# REGULADORES.net
KiCad netlist of a schematic drawn in Altium Designer
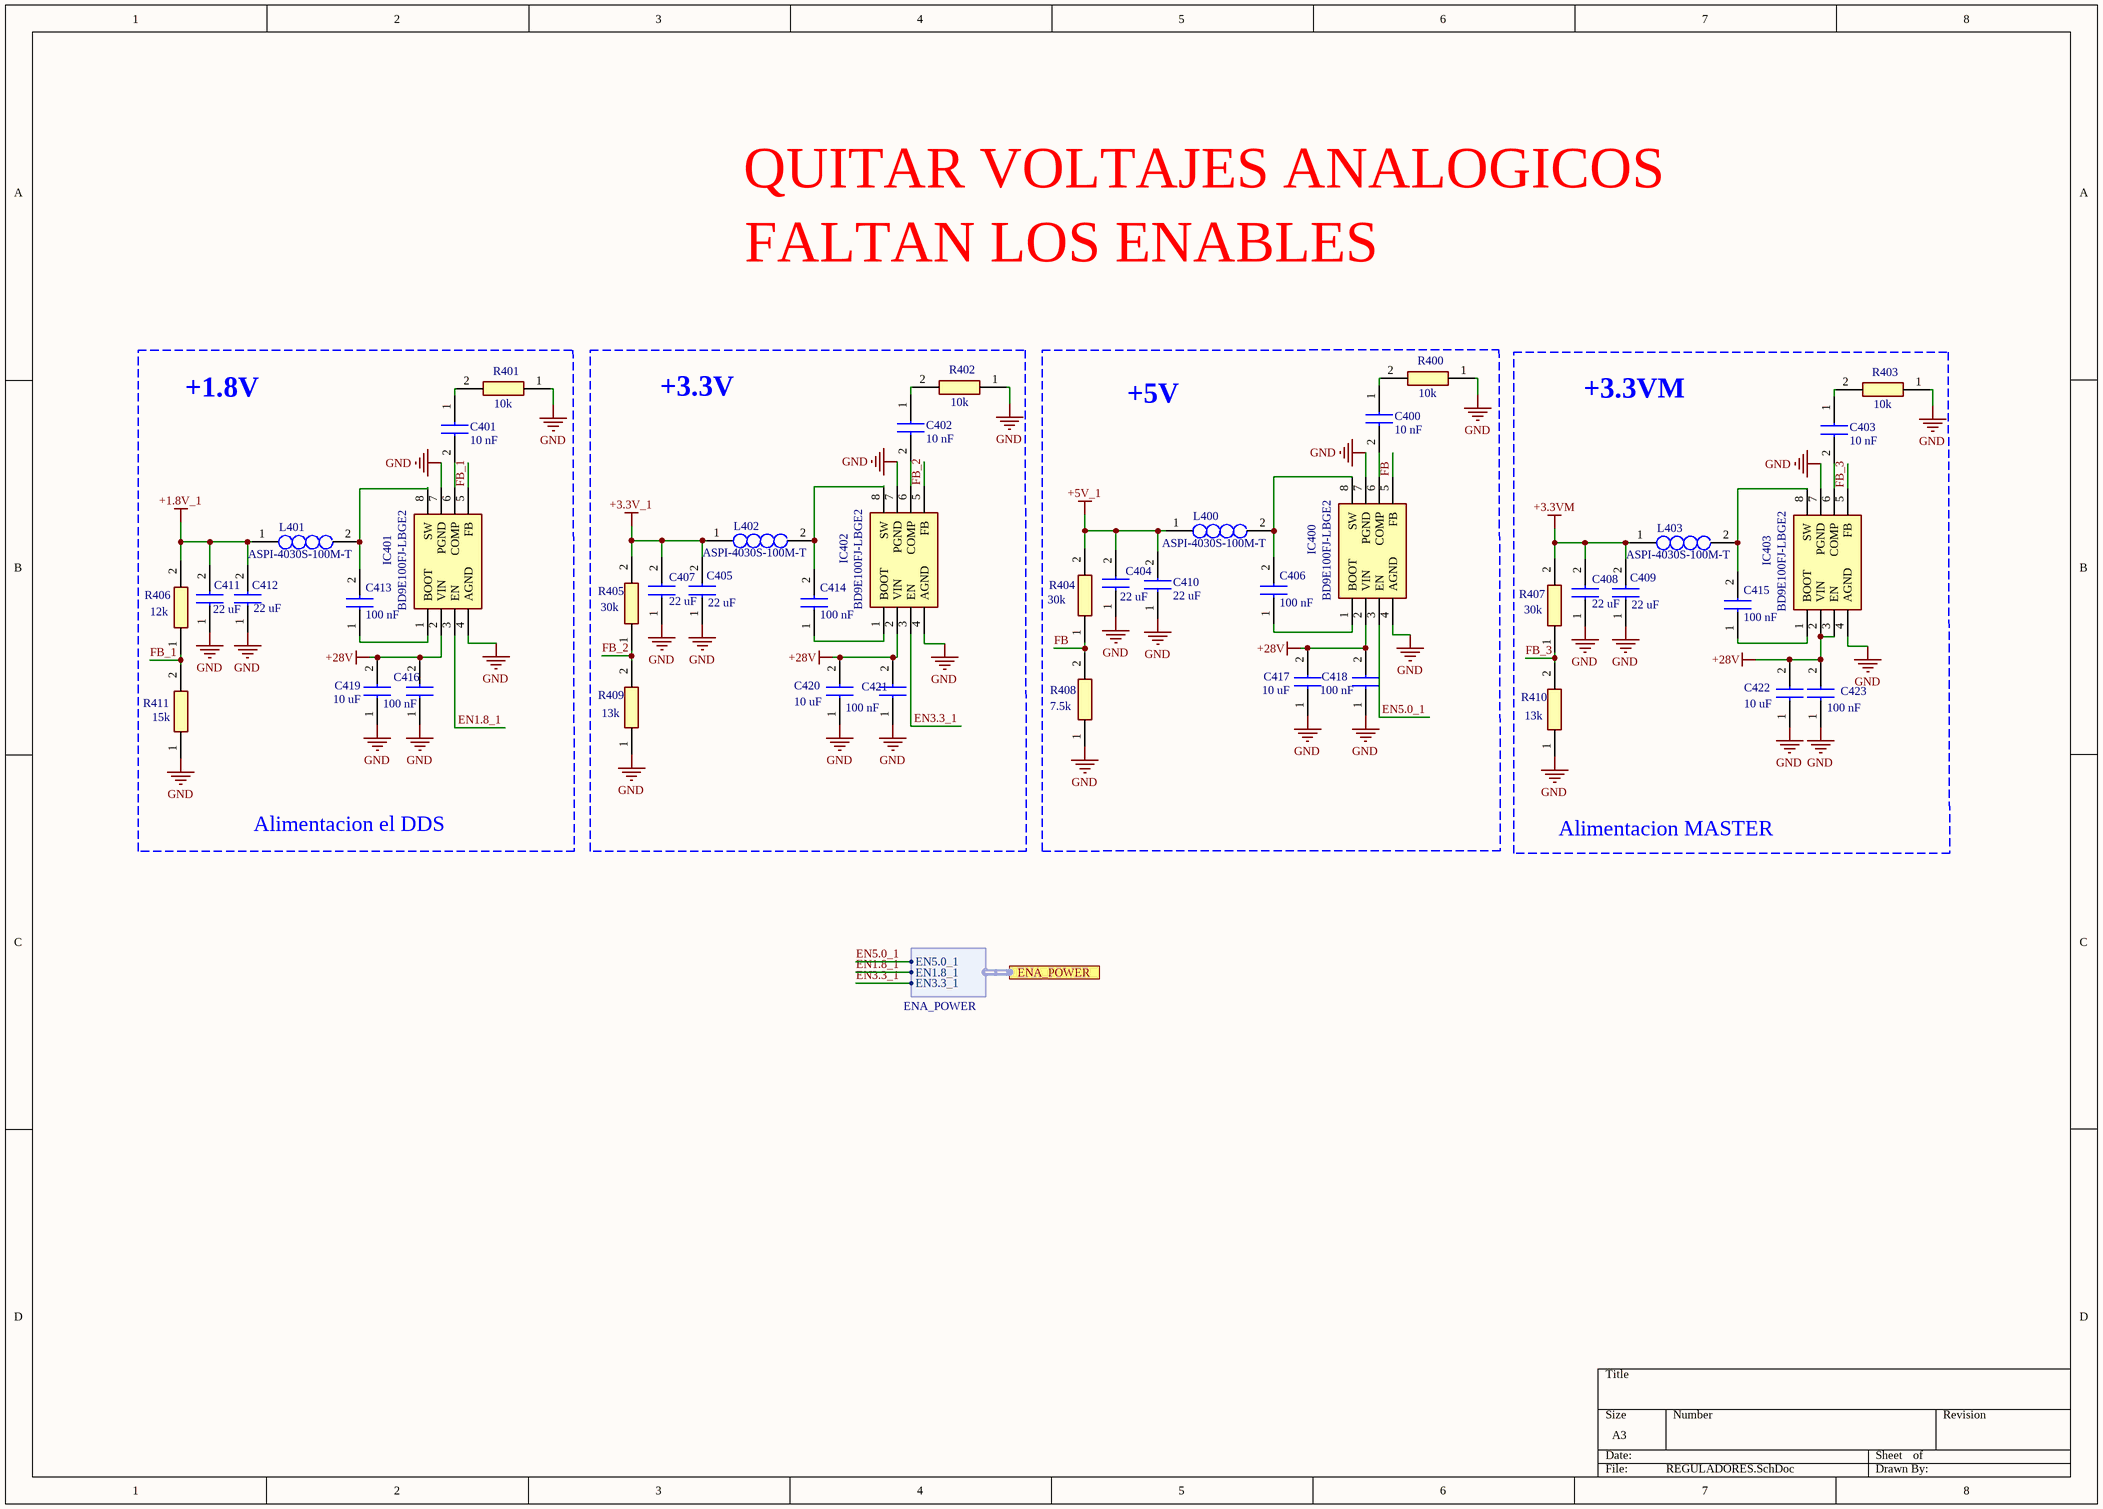
[diagram p0: REGULADORES.SchDoc]

(export (version "E")
  (design (tool "Eeschema 10.0.6"))
  (components
    (comp (ref "C400")
      (value "10 nF")
      (footprint "SamacSys:C0603")
      (description "Capacitor")
      (fields (field (name "MANUFACTURER_PART_NUMBER") "C0603H470J5GACTU"))
      (libsource (lib "*") (part "C0603H470J5GACTU"))
    )
    (comp (ref "C401")
      (value "10 nF")
      (footprint "SamacSys:C0603")
      (description "Capacitor")
      (fields (field (name "MANUFACTURER_PART_NUMBER") "C0603H470J5GACTU"))
      (libsource (lib "LIBRERIA_GEN_V2.0") (part "C0603H470J5GACTU"))
    )
    (comp (ref "C402")
      (value "10 nF")
      (footprint "SamacSys:C0603")
      (description "Capacitor")
      (fields (field (name "MANUFACTURER_PART_NUMBER") "C0603H470J5GACTU"))
      (libsource (lib "LIBRERIA_GEN_V2.0") (part "C0603H470J5GACTU"))
    )
    (comp (ref "C403")
      (value "10 nF")
      (footprint "SamacSys:C0603")
      (description "Capacitor")
      (fields (field (name "MANUFACTURER_PART_NUMBER") "C0603H470J5GACTU"))
      (libsource (lib "LIBRERIA_GEN_V2.0") (part "C0603H470J5GACTU"))
    )
    (comp (ref "C404")
      (value "22 uF")
      (footprint "SamacSys:CAPC3216X94N")
      (description "Capacitor")
      (fields
        (field (name "MANUFACTURER_PART_NUMBER") "KAM31BR81H103KT")
        (field (name "MOUSER PART NUMBER") "581-KAM31BR81H103KT")
      )
      (libsource (lib "LIBRERIA_GEN_V2.0") (part "KAM31BR81H103KT"))
    )
    (comp (ref "C405")
      (value "22 uF")
      (footprint "SamacSys:CAPC3216X94N")
      (description "Capacitor")
      (fields
        (field (name "MANUFACTURER_PART_NUMBER") "KAM31BR81H103KT")
        (field (name "MOUSER PART NUMBER") "581-KAM31BR81H103KT")
      )
      (libsource (lib "LIBRERIA_GEN_V2.0") (part "KAM31BR81H103KT"))
    )
    (comp (ref "C406")
      (value "100 nF")
      (footprint "SamacSys:C0603")
      (description "Capacitor")
      (fields (field (name "MANUFACTURER_PART_NUMBER") "C0603H470J5GACTU"))
      (libsource (lib "*") (part "C0603H470J5GACTU"))
    )
    (comp (ref "C407")
      (value "22 uF")
      (footprint "SamacSys:CAPC3216X94N")
      (description "Capacitor")
      (fields
        (field (name "MANUFACTURER_PART_NUMBER") "KAM31BR81H103KT")
        (field (name "MOUSER PART NUMBER") "581-KAM31BR81H103KT")
      )
      (libsource (lib "LIBRERIA_GEN_V2.0") (part "KAM31BR81H103KT"))
    )
    (comp (ref "C408")
      (value "22 uF")
      (footprint "SamacSys:CAPC3216X94N")
      (description "Capacitor")
      (fields
        (field (name "MANUFACTURER_PART_NUMBER") "KAM31BR81H103KT")
        (field (name "MOUSER PART NUMBER") "581-KAM31BR81H103KT")
      )
      (libsource (lib "LIBRERIA_GEN_V2.0") (part "KAM31BR81H103KT"))
    )
    (comp (ref "C409")
      (value "22 uF")
      (footprint "SamacSys:CAPC3216X94N")
      (description "Capacitor")
      (fields
        (field (name "MANUFACTURER_PART_NUMBER") "KAM31BR81H103KT")
        (field (name "MOUSER PART NUMBER") "581-KAM31BR81H103KT")
      )
      (libsource (lib "LIBRERIA_GEN_V2.0") (part "KAM31BR81H103KT"))
    )
    (comp (ref "C410")
      (value "22 uF")
      (footprint "SamacSys:CAPC3216X94N")
      (description "Capacitor")
      (fields
        (field (name "MANUFACTURER_PART_NUMBER") "KAM31BR81H103KT")
        (field (name "MOUSER PART NUMBER") "581-KAM31BR81H103KT")
      )
      (libsource (lib "LIBRERIA_GEN_V2.0") (part "KAM31BR81H103KT"))
    )
    (comp (ref "C411")
      (value "22 uF")
      (footprint "SamacSys:CAPC3216X94N")
      (description "Capacitor")
      (fields
        (field (name "MANUFACTURER_PART_NUMBER") "KAM31BR81H103KT")
        (field (name "MOUSER PART NUMBER") "581-KAM31BR81H103KT")
      )
      (libsource (lib "LIBRERIA_GEN_V2.0") (part "KAM31BR81H103KT"))
    )
    (comp (ref "C412")
      (value "22 uF")
      (footprint "SamacSys:CAPC3216X94N")
      (description "Capacitor")
      (fields
        (field (name "MANUFACTURER_PART_NUMBER") "KAM31BR81H103KT")
        (field (name "MOUSER PART NUMBER") "581-KAM31BR81H103KT")
      )
      (libsource (lib "LIBRERIA_GEN_V2.0") (part "KAM31BR81H103KT"))
    )
    (comp (ref "C413")
      (value "100 nF")
      (footprint "SamacSys:C0603")
      (description "Capacitor")
      (fields (field (name "MANUFACTURER_PART_NUMBER") "C0603H470J5GACTU"))
      (libsource (lib "LIBRERIA_GEN_V2.0") (part "C0603H470J5GACTU"))
    )
    (comp (ref "C414")
      (value "100 nF")
      (footprint "SamacSys:C0603")
      (description "Capacitor")
      (fields (field (name "MANUFACTURER_PART_NUMBER") "C0603H470J5GACTU"))
      (libsource (lib "LIBRERIA_GEN_V2.0") (part "C0603H470J5GACTU"))
    )
    (comp (ref "C415")
      (value "100 nF")
      (footprint "SamacSys:C0603")
      (description "Capacitor")
      (fields (field (name "MANUFACTURER_PART_NUMBER") "C0603H470J5GACTU"))
      (libsource (lib "LIBRERIA_GEN_V2.0") (part "C0603H470J5GACTU"))
    )
    (comp (ref "C416")
      (value "100 nF")
      (footprint "SamacSys:CAPC3216X94N")
      (description "Capacitor")
      (fields
        (field (name "MANUFACTURER_PART_NUMBER") "KAM31BR81H103KT")
        (field (name "MOUSER PART NUMBER") "581-KAM31BR81H103KT")
      )
      (libsource (lib "LIBRERIA_GEN_V2.0") (part "KAM31BR81H103KT"))
    )
    (comp (ref "C417")
      (value "10 uF")
      (footprint "SamacSys:CAPC3216X94N")
      (description "Capacitor")
      (fields
        (field (name "MANUFACTURER_PART_NUMBER") "KAM31BR81H103KT")
        (field (name "MOUSER PART NUMBER") "581-KAM31BR81H103KT")
      )
      (libsource (lib "LIBRERIA_GEN_V2.0") (part "KAM31BR81H103KT"))
    )
    (comp (ref "C418")
      (value "100 nF")
      (footprint "SamacSys:CAPC3216X94N")
      (description "Capacitor")
      (fields
        (field (name "MANUFACTURER_PART_NUMBER") "KAM31BR81H103KT")
        (field (name "MOUSER PART NUMBER") "581-KAM31BR81H103KT")
      )
      (libsource (lib "LIBRERIA_GEN_V2.0") (part "KAM31BR81H103KT"))
    )
    (comp (ref "C419")
      (value "10 uF")
      (footprint "SamacSys:CAPC3216X94N")
      (description "Capacitor")
      (fields
        (field (name "MANUFACTURER_PART_NUMBER") "KAM31BR81H103KT")
        (field (name "MOUSER PART NUMBER") "581-KAM31BR81H103KT")
      )
      (libsource (lib "LIBRERIA_GEN_V2.0") (part "KAM31BR81H103KT"))
    )
    (comp (ref "C420")
      (value "10 uF")
      (footprint "SamacSys:CAPC3216X94N")
      (description "Capacitor")
      (fields
        (field (name "MANUFACTURER_PART_NUMBER") "KAM31BR81H103KT")
        (field (name "MOUSER PART NUMBER") "581-KAM31BR81H103KT")
      )
      (libsource (lib "LIBRERIA_GEN_V2.0") (part "KAM31BR81H103KT"))
    )
    (comp (ref "C421")
      (value "100 nF")
      (footprint "SamacSys:CAPC3216X94N")
      (description "Capacitor")
      (fields
        (field (name "MANUFACTURER_PART_NUMBER") "KAM31BR81H103KT")
        (field (name "MOUSER PART NUMBER") "581-KAM31BR81H103KT")
      )
      (libsource (lib "LIBRERIA_GEN_V2.0") (part "KAM31BR81H103KT"))
    )
    (comp (ref "C422")
      (value "10 uF")
      (footprint "SamacSys:CAPC3216X94N")
      (description "Capacitor")
      (fields
        (field (name "MANUFACTURER_PART_NUMBER") "KAM31BR81H103KT")
        (field (name "MOUSER PART NUMBER") "581-KAM31BR81H103KT")
      )
      (libsource (lib "LIBRERIA_GEN_V2.0") (part "KAM31BR81H103KT"))
    )
    (comp (ref "C423")
      (value "100 nF")
      (footprint "SamacSys:CAPC3216X94N")
      (description "Capacitor")
      (fields
        (field (name "MANUFACTURER_PART_NUMBER") "KAM31BR81H103KT")
        (field (name "MOUSER PART NUMBER") "581-KAM31BR81H103KT")
      )
      (libsource (lib "LIBRERIA_GEN_V2.0") (part "KAM31BR81H103KT"))
    )
    (comp (ref "IC400")
      (value "BD9E100FJ-LBGE2")
      (footprint "SamacSys:SOIC127P600X165-8N")
      (description "Integrated Circuit")
      (fields (field (name "MOUSER PART NUMBER") "755-BD9E100FJ-LBGE2"))
      (libsource (lib "*") (part "BD9E100FJ-LBGE2"))
    )
    (comp (ref "IC401")
      (value "BD9E100FJ-LBGE2")
      (footprint "SamacSys:SOIC127P600X165-8N")
      (description "Integrated Circuit")
      (fields (field (name "MOUSER PART NUMBER") "755-BD9E100FJ-LBGE2"))
      (libsource (lib "LIBRERIA_GEN_V2.0") (part "BD9E100FJ-LBGE2"))
    )
    (comp (ref "IC402")
      (value "BD9E100FJ-LBGE2")
      (footprint "SamacSys:SOIC127P600X165-8N")
      (description "Integrated Circuit")
      (fields (field (name "MOUSER PART NUMBER") "755-BD9E100FJ-LBGE2"))
      (libsource (lib "LIBRERIA_GEN_V2.0") (part "BD9E100FJ-LBGE2"))
    )
    (comp (ref "IC403")
      (value "BD9E100FJ-LBGE2")
      (footprint "SamacSys:SOIC127P600X165-8N")
      (description "Integrated Circuit")
      (fields (field (name "MOUSER PART NUMBER") "755-BD9E100FJ-LBGE2"))
      (libsource (lib "LIBRERIA_GEN_V2.0") (part "BD9E100FJ-LBGE2"))
    )
    (comp (ref "L400")
      (value "ASPI-4030S-100M-T")
      (footprint "SamacSys:ASPI-4030S")
      (description "Inductor")
      (fields (field (name "MOUSER PART NUMBER") "815-ASPI-4030S-100MT"))
      (libsource (lib "*") (part "ASPI-4030S-100M-T"))
    )
    (comp (ref "L401")
      (value "ASPI-4030S-100M-T")
      (footprint "SamacSys:ASPI-4030S")
      (description "Inductor")
      (fields (field (name "MOUSER PART NUMBER") "815-ASPI-4030S-100MT"))
      (libsource (lib "LIBRERIA_GEN_V2.0") (part "ASPI-4030S-100M-T"))
    )
    (comp (ref "L402")
      (value "ASPI-4030S-100M-T")
      (footprint "SamacSys:ASPI-4030S")
      (description "Inductor")
      (fields (field (name "MOUSER PART NUMBER") "815-ASPI-4030S-100MT"))
      (libsource (lib "LIBRERIA_GEN_V2.0") (part "ASPI-4030S-100M-T"))
    )
    (comp (ref "L403")
      (value "ASPI-4030S-100M-T")
      (footprint "SamacSys:ASPI-4030S")
      (description "Inductor")
      (fields (field (name "MOUSER PART NUMBER") "815-ASPI-4030S-100MT"))
      (libsource (lib "LIBRERIA_GEN_V2.0") (part "ASPI-4030S-100M-T"))
    )
    (comp (ref "R400")
      (value "10k")
      (footprint "SamacSys:RESC1608X55N")
      (description "Resistor")
      (fields
        (field (name "MANUFACTURER_PART_NUMBER") "CR0603-FX-1431ELF")
        (field (name "MOUSER PART NUMBER") "652-CR0603FX-1431ELF")
      )
      (libsource (lib "*") (part "CR0603-FX-1431ELF"))
    )
    (comp (ref "R401")
      (value "10k")
      (footprint "SamacSys:RESC1608X55N")
      (description "Resistor")
      (fields
        (field (name "MANUFACTURER_PART_NUMBER") "CR0603-FX-1431ELF")
        (field (name "MOUSER PART NUMBER") "652-CR0603FX-1431ELF")
      )
      (libsource (lib "") (part "CR0603-FX-1431ELF_1"))
    )
    (comp (ref "R402")
      (value "10k")
      (footprint "SamacSys:RESC1608X55N")
      (description "Resistor")
      (fields
        (field (name "MANUFACTURER_PART_NUMBER") "CR0603-FX-1431ELF")
        (field (name "MOUSER PART NUMBER") "652-CR0603FX-1431ELF")
      )
      (libsource (lib "") (part "CR0603-FX-1431ELF_1"))
    )
    (comp (ref "R403")
      (value "10k")
      (footprint "SamacSys:RESC1608X55N")
      (description "Resistor")
      (fields
        (field (name "MANUFACTURER_PART_NUMBER") "CR0603-FX-1431ELF")
        (field (name "MOUSER PART NUMBER") "652-CR0603FX-1431ELF")
      )
      (libsource (lib "") (part "CR0603-FX-1431ELF_1"))
    )
    (comp (ref "R404")
      (value "30k")
      (footprint "SamacSys:RESC1608X55N")
      (description "Resistor")
      (fields
        (field (name "MANUFACTURER_PART_NUMBER") "CR0603-FX-1431ELF")
        (field (name "MOUSER PART NUMBER") "652-CR0603FX-1431ELF")
      )
      (libsource (lib "") (part "CR0603-FX-1431ELF_1"))
    )
    (comp (ref "R405")
      (value "30k")
      (footprint "SamacSys:RESC1608X55N")
      (description "Resistor")
      (fields
        (field (name "MANUFACTURER_PART_NUMBER") "CR0603-FX-1431ELF")
        (field (name "MOUSER PART NUMBER") "652-CR0603FX-1431ELF")
      )
      (libsource (lib "LIBRERIA_GEN_V2.0") (part "CR0603-FX-1431ELF"))
    )
    (comp (ref "R406")
      (value "12k")
      (footprint "SamacSys:RESC1608X55N")
      (description "Resistor")
      (fields
        (field (name "MANUFACTURER_PART_NUMBER") "CR0603-FX-1431ELF")
        (field (name "MOUSER PART NUMBER") "652-CR0603FX-1431ELF")
      )
      (libsource (lib "LIBRERIA_GEN_V2.0") (part "CR0603-FX-1431ELF"))
    )
    (comp (ref "R407")
      (value "30k")
      (footprint "SamacSys:RESC1608X55N")
      (description "Resistor")
      (fields
        (field (name "MANUFACTURER_PART_NUMBER") "CR0603-FX-1431ELF")
        (field (name "MOUSER PART NUMBER") "652-CR0603FX-1431ELF")
      )
      (libsource (lib "LIBRERIA_GEN_V2.0") (part "CR0603-FX-1431ELF"))
    )
    (comp (ref "R408")
      (value "7.5k")
      (footprint "SamacSys:RESC1608X55N")
      (description "Resistor")
      (fields
        (field (name "MANUFACTURER_PART_NUMBER") "CR0603-FX-1431ELF")
        (field (name "MOUSER PART NUMBER") "652-CR0603FX-1431ELF")
      )
      (libsource (lib "") (part "CR0603-FX-1431ELF_1"))
    )
    (comp (ref "R409")
      (value "13k")
      (footprint "SamacSys:RESC1608X55N")
      (description "Resistor")
      (fields
        (field (name "MANUFACTURER_PART_NUMBER") "CR0603-FX-1431ELF")
        (field (name "MOUSER PART NUMBER") "652-CR0603FX-1431ELF")
      )
      (libsource (lib "LIBRERIA_GEN_V2.0") (part "CR0603-FX-1431ELF"))
    )
    (comp (ref "R410")
      (value "13k")
      (footprint "SamacSys:RESC1608X55N")
      (description "Resistor")
      (fields
        (field (name "MANUFACTURER_PART_NUMBER") "CR0603-FX-1431ELF")
        (field (name "MOUSER PART NUMBER") "652-CR0603FX-1431ELF")
      )
      (libsource (lib "LIBRERIA_GEN_V2.0") (part "CR0603-FX-1431ELF"))
    )
    (comp (ref "R411")
      (value "15k")
      (footprint "SamacSys:RESC1608X55N")
      (description "Resistor")
      (fields
        (field (name "MANUFACTURER_PART_NUMBER") "CR0603-FX-1431ELF")
        (field (name "MOUSER PART NUMBER") "652-CR0603FX-1431ELF")
      )
      (libsource (lib "LIBRERIA_GEN_V2.0") (part "CR0603-FX-1431ELF"))
    )
  )
  (nets
    (net (code "2") (name "+1.8V_1") (class "Default")
      (node (ref "C411") (pin "2") (pinfunction "2_2") (pintype "passive"))
      (node (ref "C412") (pin "2") (pinfunction "2_2") (pintype "passive"))
      (node (ref "L401") (pin "1") (pinfunction "1_1") (pintype "passive"))
      (node (ref "R406") (pin "2") (pinfunction "2_2") (pintype "passive"))
    )
    (net (code "3") (name "+3.3VM") (class "Default")
      (node (ref "C408") (pin "2") (pinfunction "2_2") (pintype "passive"))
      (node (ref "C409") (pin "2") (pinfunction "2_2") (pintype "passive"))
      (node (ref "L403") (pin "1") (pinfunction "1_1") (pintype "passive"))
      (node (ref "R407") (pin "2") (pinfunction "2_2") (pintype "passive"))
    )
    (net (code "4") (name "+3.3V_1") (class "Default")
      (node (ref "C405") (pin "2") (pinfunction "2_2") (pintype "passive"))
      (node (ref "C407") (pin "2") (pinfunction "2_2") (pintype "passive"))
      (node (ref "L402") (pin "1") (pinfunction "1_1") (pintype "passive"))
      (node (ref "R405") (pin "2") (pinfunction "2_2") (pintype "passive"))
    )
    (net (code "5") (name "+5V_1") (class "Default")
      (node (ref "C404") (pin "2") (pinfunction "2_2") (pintype "passive"))
      (node (ref "C410") (pin "2") (pinfunction "2_2") (pintype "passive"))
      (node (ref "L400") (pin "1") (pinfunction "1_1") (pintype "passive"))
      (node (ref "R404") (pin "2") (pinfunction "2_2") (pintype "passive"))
    )
    (net (code "6") (name "+28V") (class "Default")
      (node (ref "C416") (pin "2") (pinfunction "2_2") (pintype "passive"))
      (node (ref "C417") (pin "2") (pinfunction "2_2") (pintype "passive"))
      (node (ref "C418") (pin "2") (pinfunction "2_2") (pintype "passive"))
      (node (ref "C419") (pin "2") (pinfunction "2_2") (pintype "passive"))
      (node (ref "C420") (pin "2") (pinfunction "2_2") (pintype "passive"))
      (node (ref "C421") (pin "2") (pinfunction "2_2") (pintype "passive"))
      (node (ref "C422") (pin "2") (pinfunction "2_2") (pintype "passive"))
      (node (ref "C423") (pin "2") (pinfunction "2_2") (pintype "passive"))
      (node (ref "IC400") (pin "2") (pinfunction "VIN_2") (pintype "passive"))
      (node (ref "IC401") (pin "2") (pinfunction "VIN_2") (pintype "passive"))
      (node (ref "IC402") (pin "2") (pinfunction "VIN_2") (pintype "passive"))
      (node (ref "IC403") (pin "2") (pinfunction "VIN_2") (pintype "passive"))
      (node (ref "IC403") (pin "3") (pinfunction "EN_3") (pintype "passive"))
    )
    (net (code "7") (name "/EN1.8_1") (class "Default")
      (node (ref "IC401") (pin "3") (pinfunction "EN_3") (pintype "passive"))
    )
    (net (code "8") (name "/EN3.3_1") (class "Default")
      (node (ref "IC402") (pin "3") (pinfunction "EN_3") (pintype "passive"))
    )
    (net (code "9") (name "/EN5.0_1") (class "Default")
      (node (ref "IC400") (pin "3") (pinfunction "EN_3") (pintype "passive"))
    )
    (net (code "10") (name "/FB") (class "Default")
      (node (ref "IC400") (pin "5") (pinfunction "FB_5") (pintype "passive"))
      (node (ref "R404") (pin "1") (pinfunction "1_1") (pintype "passive"))
      (node (ref "R408") (pin "2") (pinfunction "2_2") (pintype "passive"))
    )
    (net (code "11") (name "/FB_1") (class "Default")
      (node (ref "IC401") (pin "5") (pinfunction "FB_5") (pintype "passive"))
      (node (ref "R406") (pin "1") (pinfunction "1_1") (pintype "passive"))
      (node (ref "R411") (pin "2") (pinfunction "2_2") (pintype "passive"))
    )
    (net (code "12") (name "/FB_2") (class "Default")
      (node (ref "IC402") (pin "5") (pinfunction "FB_5") (pintype "passive"))
      (node (ref "R405") (pin "1") (pinfunction "1_1") (pintype "passive"))
      (node (ref "R409") (pin "2") (pinfunction "2_2") (pintype "passive"))
    )
    (net (code "13") (name "/FB_3") (class "Default")
      (node (ref "IC403") (pin "5") (pinfunction "FB_5") (pintype "passive"))
      (node (ref "R407") (pin "1") (pinfunction "1_1") (pintype "passive"))
      (node (ref "R410") (pin "2") (pinfunction "2_2") (pintype "passive"))
    )
    (net (code "15") (name "GND") (class "Default")
      (node (ref "C404") (pin "1") (pinfunction "1_1") (pintype "passive"))
      (node (ref "C405") (pin "1") (pinfunction "1_1") (pintype "passive"))
      (node (ref "C407") (pin "1") (pinfunction "1_1") (pintype "passive"))
      (node (ref "C408") (pin "1") (pinfunction "1_1") (pintype "passive"))
      (node (ref "C409") (pin "1") (pinfunction "1_1") (pintype "passive"))
      (node (ref "C410") (pin "1") (pinfunction "1_1") (pintype "passive"))
      (node (ref "C411") (pin "1") (pinfunction "1_1") (pintype "passive"))
      (node (ref "C412") (pin "1") (pinfunction "1_1") (pintype "passive"))
      (node (ref "C416") (pin "1") (pinfunction "1_1") (pintype "passive"))
      (node (ref "C417") (pin "1") (pinfunction "1_1") (pintype "passive"))
      (node (ref "C418") (pin "1") (pinfunction "1_1") (pintype "passive"))
      (node (ref "C419") (pin "1") (pinfunction "1_1") (pintype "passive"))
      (node (ref "C420") (pin "1") (pinfunction "1_1") (pintype "passive"))
      (node (ref "C421") (pin "1") (pinfunction "1_1") (pintype "passive"))
      (node (ref "C422") (pin "1") (pinfunction "1_1") (pintype "passive"))
      (node (ref "C423") (pin "1") (pinfunction "1_1") (pintype "passive"))
      (node (ref "IC400") (pin "4") (pinfunction "AGND_4") (pintype "passive"))
      (node (ref "IC400") (pin "7") (pinfunction "PGND_7") (pintype "passive"))
      (node (ref "IC401") (pin "4") (pinfunction "AGND_4") (pintype "passive"))
      (node (ref "IC401") (pin "7") (pinfunction "PGND_7") (pintype "passive"))
      (node (ref "IC402") (pin "4") (pinfunction "AGND_4") (pintype "passive"))
      (node (ref "IC402") (pin "7") (pinfunction "PGND_7") (pintype "passive"))
      (node (ref "IC403") (pin "4") (pinfunction "AGND_4") (pintype "passive"))
      (node (ref "IC403") (pin "7") (pinfunction "PGND_7") (pintype "passive"))
      (node (ref "R400") (pin "1") (pinfunction "1_1") (pintype "passive"))
      (node (ref "R401") (pin "1") (pinfunction "1_1") (pintype "passive"))
      (node (ref "R402") (pin "1") (pinfunction "1_1") (pintype "passive"))
      (node (ref "R403") (pin "1") (pinfunction "1_1") (pintype "passive"))
      (node (ref "R408") (pin "1") (pinfunction "1_1") (pintype "passive"))
      (node (ref "R409") (pin "1") (pinfunction "1_1") (pintype "passive"))
      (node (ref "R410") (pin "1") (pinfunction "1_1") (pintype "passive"))
      (node (ref "R411") (pin "1") (pinfunction "1_1") (pintype "passive"))
    )
    (net (code "16") (name "Net-(C400-Pad1)") (class "Default")
      (node (ref "C400") (pin "1") (pinfunction "1_1") (pintype "passive"))
      (node (ref "R400") (pin "2") (pinfunction "2_2") (pintype "passive"))
    )
    (net (code "17") (name "Net-(C401-Pad1)") (class "Default")
      (node (ref "C401") (pin "1") (pinfunction "1_1") (pintype "passive"))
      (node (ref "R401") (pin "2") (pinfunction "2_2") (pintype "passive"))
    )
    (net (code "18") (name "Net-(C402-Pad1)") (class "Default")
      (node (ref "C402") (pin "1") (pinfunction "1_1") (pintype "passive"))
      (node (ref "R402") (pin "2") (pinfunction "2_2") (pintype "passive"))
    )
    (net (code "19") (name "Net-(C403-Pad1)") (class "Default")
      (node (ref "C403") (pin "1") (pinfunction "1_1") (pintype "passive"))
      (node (ref "R403") (pin "2") (pinfunction "2_2") (pintype "passive"))
    )
    (net (code "20") (name "Net-(IC400-BOOT)") (class "Default")
      (node (ref "C406") (pin "1") (pinfunction "1_1") (pintype "passive"))
      (node (ref "IC400") (pin "1") (pinfunction "BOOT_1") (pintype "passive"))
    )
    (net (code "21") (name "Net-(IC400-COMP)") (class "Default")
      (node (ref "C400") (pin "2") (pinfunction "2_2") (pintype "passive"))
      (node (ref "IC400") (pin "6") (pinfunction "COMP_6") (pintype "passive"))
    )
    (net (code "22") (name "Net-(IC400-SW)") (class "Default")
      (node (ref "C406") (pin "2") (pinfunction "2_2") (pintype "passive"))
      (node (ref "IC400") (pin "8") (pinfunction "SW_8") (pintype "passive"))
      (node (ref "L400") (pin "2") (pinfunction "2_2") (pintype "passive"))
    )
    (net (code "23") (name "Net-(IC401-BOOT)") (class "Default")
      (node (ref "C413") (pin "1") (pinfunction "1_1") (pintype "passive"))
      (node (ref "IC401") (pin "1") (pinfunction "BOOT_1") (pintype "passive"))
    )
    (net (code "24") (name "Net-(IC401-COMP)") (class "Default")
      (node (ref "C401") (pin "2") (pinfunction "2_2") (pintype "passive"))
      (node (ref "IC401") (pin "6") (pinfunction "COMP_6") (pintype "passive"))
    )
    (net (code "25") (name "Net-(IC401-SW)") (class "Default")
      (node (ref "C413") (pin "2") (pinfunction "2_2") (pintype "passive"))
      (node (ref "IC401") (pin "8") (pinfunction "SW_8") (pintype "passive"))
      (node (ref "L401") (pin "2") (pinfunction "2_2") (pintype "passive"))
    )
    (net (code "26") (name "Net-(IC402-BOOT)") (class "Default")
      (node (ref "C414") (pin "1") (pinfunction "1_1") (pintype "passive"))
      (node (ref "IC402") (pin "1") (pinfunction "BOOT_1") (pintype "passive"))
    )
    (net (code "27") (name "Net-(IC402-COMP)") (class "Default")
      (node (ref "C402") (pin "2") (pinfunction "2_2") (pintype "passive"))
      (node (ref "IC402") (pin "6") (pinfunction "COMP_6") (pintype "passive"))
    )
    (net (code "28") (name "Net-(IC402-SW)") (class "Default")
      (node (ref "C414") (pin "2") (pinfunction "2_2") (pintype "passive"))
      (node (ref "IC402") (pin "8") (pinfunction "SW_8") (pintype "passive"))
      (node (ref "L402") (pin "2") (pinfunction "2_2") (pintype "passive"))
    )
    (net (code "29") (name "Net-(IC403-BOOT)") (class "Default")
      (node (ref "C415") (pin "1") (pinfunction "1_1") (pintype "passive"))
      (node (ref "IC403") (pin "1") (pinfunction "BOOT_1") (pintype "passive"))
    )
    (net (code "30") (name "Net-(IC403-COMP)") (class "Default")
      (node (ref "C403") (pin "2") (pinfunction "2_2") (pintype "passive"))
      (node (ref "IC403") (pin "6") (pinfunction "COMP_6") (pintype "passive"))
    )
    (net (code "31") (name "Net-(IC403-SW)") (class "Default")
      (node (ref "C415") (pin "2") (pinfunction "2_2") (pintype "passive"))
      (node (ref "IC403") (pin "8") (pinfunction "SW_8") (pintype "passive"))
      (node (ref "L403") (pin "2") (pinfunction "2_2") (pintype "passive"))
    )
  )
)
